# raspilot.net
KiCad netlist of a schematic drawn in EAGLE
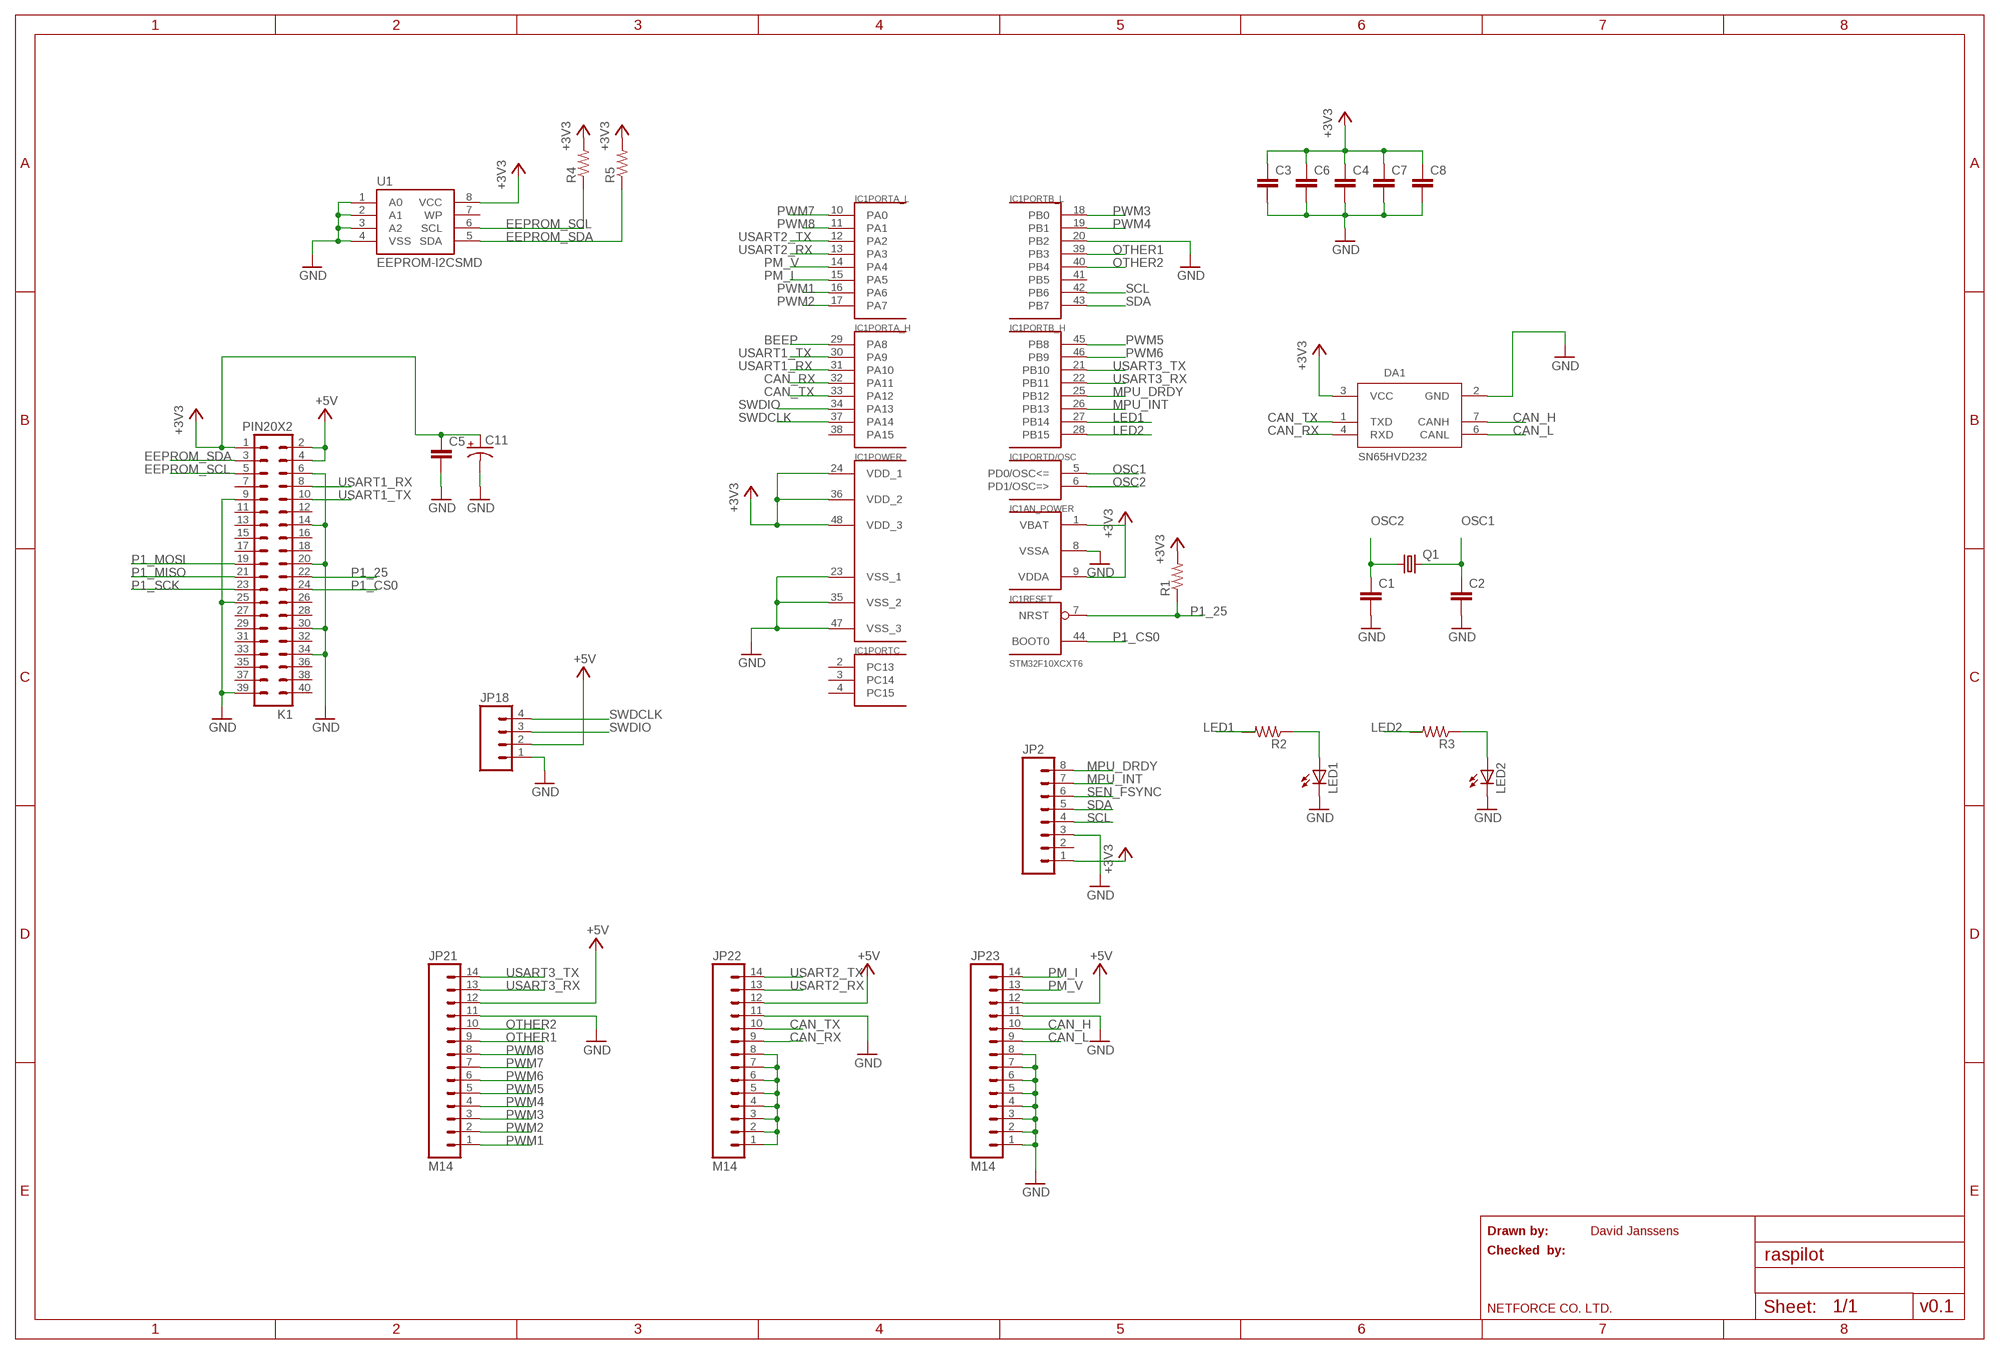
[diagram p0: schematic, sheet 1]

(export (version "E")
  (design (tool "Eeschema 10.0.6"))
  (components
    (comp (ref "C1")
      (value "CAP0805")
      (footprint "eagle-import:0805")
      (libsource (lib "eagle-import") (part "CAP0805"))
    )
    (comp (ref "C2")
      (value "CAP0805")
      (footprint "eagle-import:0805")
      (libsource (lib "eagle-import") (part "CAP0805"))
    )
    (comp (ref "C3")
      (value "CAP0805")
      (footprint "eagle-import:0805")
      (libsource (lib "eagle-import") (part "CAP0805"))
    )
    (comp (ref "C4")
      (value "CAP0805")
      (footprint "eagle-import:0805")
      (libsource (lib "eagle-import") (part "CAP0805"))
    )
    (comp (ref "C5")
      (value "CAP0805")
      (footprint "eagle-import:0805")
      (libsource (lib "eagle-import") (part "CAP0805"))
    )
    (comp (ref "C6")
      (value "CAP0805")
      (footprint "eagle-import:0805")
      (libsource (lib "eagle-import") (part "CAP0805"))
    )
    (comp (ref "C7")
      (value "CAP0805")
      (footprint "eagle-import:0805")
      (libsource (lib "eagle-import") (part "CAP0805"))
    )
    (comp (ref "C8")
      (value "CAP0805")
      (footprint "eagle-import:0805")
      (libsource (lib "eagle-import") (part "CAP0805"))
    )
    (comp (ref "C11")
      (value "CPOL-USE2.5-6")
      (footprint "eagle-import:E2,5-6")
      (libsource (lib "eagle-import") (part "CPOL-USE2.5-6"))
    )
    (comp (ref "DA1")
      (value "SN65HVD232")
      (footprint "eagle-import:SO08")
      (libsource (lib "eagle-import") (part "SN65HVD232"))
    )
    (comp (ref "IC1")
      (value "STM32F10XCXT6")
      (footprint "eagle-import:TQFP48")
      (libsource (lib "eagle-import") (part "STM32F10XCXT6"))
    )
    (comp (ref "JP2")
      (value "M08")
      (footprint "eagle-import:1X08_ROUND")
      (libsource (lib "eagle-import") (part "M08"))
    )
    (comp (ref "JP18")
      (value "M04PTH")
      (footprint "eagle-import:1X04")
      (libsource (lib "eagle-import") (part "M04PTH"))
    )
    (comp (ref "JP21")
      (value "M14")
      (footprint "eagle-import:1X14")
      (libsource (lib "eagle-import") (part "M14"))
    )
    (comp (ref "JP22")
      (value "M14")
      (footprint "eagle-import:1X14")
      (libsource (lib "eagle-import") (part "M14"))
    )
    (comp (ref "JP23")
      (value "M14")
      (footprint "eagle-import:1X14")
      (libsource (lib "eagle-import") (part "M14"))
    )
    (comp (ref "K1")
      (value "PIN20X2")
      (footprint "eagle-import:PIN_20X2")
      (libsource (lib "eagle-import") (part "PIN20X2"))
    )
    (comp (ref "LED1")
      (value "LED3MM")
      (footprint "eagle-import:LED3MM")
      (libsource (lib "eagle-import") (part "LED3MM"))
    )
    (comp (ref "LED2")
      (value "LED3MM")
      (footprint "eagle-import:LED3MM")
      (libsource (lib "eagle-import") (part "LED3MM"))
    )
    (comp (ref "Q1")
      (value "CRYSTALHC49S")
      (footprint "eagle-import:HC49_S")
      (libsource (lib "eagle-import") (part "CRYSTALHC49S"))
    )
    (comp (ref "R1")
      (value "RESISTOR0805-RES")
      (footprint "eagle-import:0805")
      (libsource (lib "eagle-import") (part "RESISTOR0805-RES"))
    )
    (comp (ref "R2")
      (value "RESISTOR0805-RES")
      (footprint "eagle-import:0805")
      (libsource (lib "eagle-import") (part "RESISTOR0805-RES"))
    )
    (comp (ref "R3")
      (value "RESISTOR0805-RES")
      (footprint "eagle-import:0805")
      (libsource (lib "eagle-import") (part "RESISTOR0805-RES"))
    )
    (comp (ref "R4")
      (value "RESISTOR0805-RES")
      (footprint "eagle-import:0805")
      (libsource (lib "eagle-import") (part "RESISTOR0805-RES"))
    )
    (comp (ref "R5")
      (value "RESISTOR0805-RES")
      (footprint "eagle-import:0805")
      (libsource (lib "eagle-import") (part "RESISTOR0805-RES"))
    )
    (comp (ref "U1")
      (value "EEPROM-I2CSMD")
      (footprint "eagle-import:SO08")
      (libsource (lib "eagle-import") (part "EEPROM-I2CSMD"))
    )
  )
  (nets
    (net (code "1") (name "+3V3") (class "Default")
      (node (ref "C11") (pin "+") (pinfunction "+_+") (pintype "passive"))
      (node (ref "C3") (pin "1") (pinfunction "1_1") (pintype "passive"))
      (node (ref "C4") (pin "1") (pinfunction "1_1") (pintype "passive"))
      (node (ref "C5") (pin "1") (pinfunction "1_1") (pintype "passive"))
      (node (ref "C6") (pin "1") (pinfunction "1_1") (pintype "passive"))
      (node (ref "C7") (pin "1") (pinfunction "1_1") (pintype "passive"))
      (node (ref "C8") (pin "1") (pinfunction "1_1") (pintype "passive"))
      (node (ref "DA1") (pin "3") (pinfunction "VCC_3") (pintype "power_in"))
      (node (ref "IC1") (pin "1") (pinfunction "VBAT_1") (pintype "power_in"))
      (node (ref "IC1") (pin "24") (pinfunction "VDD_1_24") (pintype "power_in"))
      (node (ref "IC1") (pin "36") (pinfunction "VDD_2_36") (pintype "power_in"))
      (node (ref "IC1") (pin "48") (pinfunction "VDD_3_48") (pintype "power_in"))
      (node (ref "IC1") (pin "9") (pinfunction "VDDA_9") (pintype "power_in"))
      (node (ref "JP2") (pin "1") (pinfunction "1_1") (pintype "passive"))
      (node (ref "K1") (pin "1") (pinfunction "1_1") (pintype "passive"))
      (node (ref "R1") (pin "2") (pinfunction "2_2") (pintype "passive"))
      (node (ref "R4") (pin "2") (pinfunction "2_2") (pintype "passive"))
      (node (ref "R5") (pin "2") (pinfunction "2_2") (pintype "passive"))
      (node (ref "U1") (pin "8") (pinfunction "VCC_8") (pintype "power_in"))
    )
    (net (code "2") (name "+5V") (class "Default")
      (node (ref "JP18") (pin "2") (pinfunction "2_2") (pintype "passive"))
      (node (ref "JP21") (pin "12") (pinfunction "12_12") (pintype "passive"))
      (node (ref "JP22") (pin "12") (pinfunction "12_12") (pintype "passive"))
      (node (ref "JP23") (pin "12") (pinfunction "12_12") (pintype "passive"))
      (node (ref "K1") (pin "2") (pinfunction "2_2") (pintype "passive"))
      (node (ref "K1") (pin "4") (pinfunction "4_4") (pintype "passive"))
    )
    (net (code "3") (name "/BEEP") (class "Default")
      (node (ref "IC1") (pin "29") (pinfunction "PA8_29") (pintype "bidirectional"))
    )
    (net (code "4") (name "/CAN_H") (class "Default")
      (node (ref "DA1") (pin "7") (pinfunction "CANH_7") (pintype "bidirectional"))
      (node (ref "JP23") (pin "10") (pinfunction "10_10") (pintype "passive"))
    )
    (net (code "5") (name "/CAN_L") (class "Default")
      (node (ref "DA1") (pin "6") (pinfunction "CANL_6") (pintype "bidirectional"))
      (node (ref "JP23") (pin "9") (pinfunction "9_9") (pintype "passive"))
    )
    (net (code "6") (name "/CAN_RX") (class "Default")
      (node (ref "DA1") (pin "4") (pinfunction "RXD_4") (pintype "output"))
      (node (ref "IC1") (pin "32") (pinfunction "PA11_32") (pintype "bidirectional"))
      (node (ref "JP22") (pin "9") (pinfunction "9_9") (pintype "passive"))
    )
    (net (code "7") (name "/CAN_TX") (class "Default")
      (node (ref "DA1") (pin "1") (pinfunction "TXD_1") (pintype "input"))
      (node (ref "IC1") (pin "33") (pinfunction "PA12_33") (pintype "bidirectional"))
      (node (ref "JP22") (pin "10") (pinfunction "10_10") (pintype "passive"))
    )
    (net (code "8") (name "/EEPROM_SCL") (class "Default")
      (node (ref "K1") (pin "5") (pinfunction "5_5") (pintype "passive"))
      (node (ref "R4") (pin "1") (pinfunction "1_1") (pintype "passive"))
      (node (ref "U1") (pin "6") (pinfunction "SCL_6") (pintype "bidirectional"))
    )
    (net (code "9") (name "/EEPROM_SDA") (class "Default")
      (node (ref "K1") (pin "3") (pinfunction "3_3") (pintype "passive"))
      (node (ref "R5") (pin "1") (pinfunction "1_1") (pintype "passive"))
      (node (ref "U1") (pin "5") (pinfunction "SDA_5") (pintype "bidirectional"))
    )
    (net (code "10") (name "/LED1") (class "Default")
      (node (ref "IC1") (pin "27") (pinfunction "PB14_27") (pintype "bidirectional"))
      (node (ref "R2") (pin "2") (pinfunction "2_2") (pintype "passive"))
    )
    (net (code "11") (name "/LED2") (class "Default")
      (node (ref "IC1") (pin "28") (pinfunction "PB15_28") (pintype "bidirectional"))
      (node (ref "R3") (pin "2") (pinfunction "2_2") (pintype "passive"))
    )
    (net (code "12") (name "/MPU_DRDY") (class "Default")
      (node (ref "IC1") (pin "25") (pinfunction "PB12_25") (pintype "bidirectional"))
      (node (ref "JP2") (pin "8") (pinfunction "8_8") (pintype "passive"))
    )
    (net (code "13") (name "/MPU_INT") (class "Default")
      (node (ref "IC1") (pin "26") (pinfunction "PB13_26") (pintype "bidirectional"))
      (node (ref "JP2") (pin "7") (pinfunction "7_7") (pintype "passive"))
    )
    (net (code "14") (name "/OSC1") (class "Default")
      (node (ref "C2") (pin "1") (pinfunction "1_1") (pintype "passive"))
      (node (ref "IC1") (pin "5") (pinfunction "PD0/OSC<=_5") (pintype "bidirectional"))
      (node (ref "Q1") (pin "2") (pinfunction "2_2") (pintype "passive"))
    )
    (net (code "15") (name "/OSC2") (class "Default")
      (node (ref "C1") (pin "1") (pinfunction "1_1") (pintype "passive"))
      (node (ref "IC1") (pin "6") (pinfunction "PD1/OSC=>_6") (pintype "bidirectional"))
      (node (ref "Q1") (pin "1") (pinfunction "1_1") (pintype "passive"))
    )
    (net (code "16") (name "/OTHER1") (class "Default")
      (node (ref "IC1") (pin "39") (pinfunction "PB3_39") (pintype "bidirectional"))
      (node (ref "JP21") (pin "9") (pinfunction "9_9") (pintype "passive"))
    )
    (net (code "17") (name "/OTHER2") (class "Default")
      (node (ref "IC1") (pin "40") (pinfunction "PB4_40") (pintype "bidirectional"))
      (node (ref "JP21") (pin "10") (pinfunction "10_10") (pintype "passive"))
    )
    (net (code "18") (name "/P1_25") (class "Default")
      (node (ref "IC1") (pin "7") (pinfunction "NRST_7") (pintype "input"))
      (node (ref "K1") (pin "22") (pinfunction "22_22") (pintype "passive"))
      (node (ref "R1") (pin "1") (pinfunction "1_1") (pintype "passive"))
    )
    (net (code "19") (name "/P1_CS0") (class "Default")
      (node (ref "IC1") (pin "44") (pinfunction "BOOT0_44") (pintype "input"))
      (node (ref "K1") (pin "24") (pinfunction "24_24") (pintype "passive"))
    )
    (net (code "20") (name "/P1_MISO") (class "Default")
      (node (ref "K1") (pin "21") (pinfunction "21_21") (pintype "passive"))
    )
    (net (code "21") (name "/P1_MOSI") (class "Default")
      (node (ref "K1") (pin "19") (pinfunction "19_19") (pintype "passive"))
    )
    (net (code "22") (name "/P1_SCK") (class "Default")
      (node (ref "K1") (pin "23") (pinfunction "23_23") (pintype "passive"))
    )
    (net (code "23") (name "/PM_I") (class "Default")
      (node (ref "IC1") (pin "15") (pinfunction "PA5_15") (pintype "bidirectional"))
      (node (ref "JP23") (pin "14") (pinfunction "14_14") (pintype "passive"))
    )
    (net (code "24") (name "/PM_V") (class "Default")
      (node (ref "IC1") (pin "14") (pinfunction "PA4_14") (pintype "bidirectional"))
      (node (ref "JP23") (pin "13") (pinfunction "13_13") (pintype "passive"))
    )
    (net (code "25") (name "/PWM1") (class "Default")
      (node (ref "IC1") (pin "16") (pinfunction "PA6_16") (pintype "bidirectional"))
      (node (ref "JP21") (pin "1") (pinfunction "1_1") (pintype "passive"))
    )
    (net (code "26") (name "/PWM2") (class "Default")
      (node (ref "IC1") (pin "17") (pinfunction "PA7_17") (pintype "bidirectional"))
      (node (ref "JP21") (pin "2") (pinfunction "2_2") (pintype "passive"))
    )
    (net (code "27") (name "/PWM3") (class "Default")
      (node (ref "IC1") (pin "18") (pinfunction "PB0_18") (pintype "bidirectional"))
      (node (ref "JP21") (pin "3") (pinfunction "3_3") (pintype "passive"))
    )
    (net (code "28") (name "/PWM4") (class "Default")
      (node (ref "IC1") (pin "19") (pinfunction "PB1_19") (pintype "bidirectional"))
      (node (ref "JP21") (pin "4") (pinfunction "4_4") (pintype "passive"))
    )
    (net (code "29") (name "/PWM5") (class "Default")
      (node (ref "IC1") (pin "45") (pinfunction "PB8_45") (pintype "bidirectional"))
      (node (ref "JP21") (pin "5") (pinfunction "5_5") (pintype "passive"))
    )
    (net (code "30") (name "/PWM6") (class "Default")
      (node (ref "IC1") (pin "46") (pinfunction "PB9_46") (pintype "bidirectional"))
      (node (ref "JP21") (pin "6") (pinfunction "6_6") (pintype "passive"))
    )
    (net (code "31") (name "/PWM7") (class "Default")
      (node (ref "IC1") (pin "10") (pinfunction "PA0_10") (pintype "bidirectional"))
      (node (ref "JP21") (pin "7") (pinfunction "7_7") (pintype "passive"))
    )
    (net (code "32") (name "/PWM8") (class "Default")
      (node (ref "IC1") (pin "11") (pinfunction "PA1_11") (pintype "bidirectional"))
      (node (ref "JP21") (pin "8") (pinfunction "8_8") (pintype "passive"))
    )
    (net (code "33") (name "/SCL") (class "Default")
      (node (ref "IC1") (pin "42") (pinfunction "PB6_42") (pintype "bidirectional"))
      (node (ref "JP2") (pin "4") (pinfunction "4_4") (pintype "passive"))
    )
    (net (code "34") (name "/SDA") (class "Default")
      (node (ref "IC1") (pin "43") (pinfunction "PB7_43") (pintype "bidirectional"))
      (node (ref "JP2") (pin "5") (pinfunction "5_5") (pintype "passive"))
    )
    (net (code "35") (name "/SEN_FSYNC") (class "Default")
      (node (ref "JP2") (pin "6") (pinfunction "6_6") (pintype "passive"))
    )
    (net (code "36") (name "/SWDCLK") (class "Default")
      (node (ref "IC1") (pin "37") (pinfunction "PA14_37") (pintype "bidirectional"))
      (node (ref "JP18") (pin "4") (pinfunction "4_4") (pintype "passive"))
    )
    (net (code "37") (name "/SWDIO") (class "Default")
      (node (ref "IC1") (pin "34") (pinfunction "PA13_34") (pintype "bidirectional"))
      (node (ref "JP18") (pin "3") (pinfunction "3_3") (pintype "passive"))
    )
    (net (code "38") (name "/USART1_RX") (class "Default")
      (node (ref "IC1") (pin "31") (pinfunction "PA10_31") (pintype "bidirectional"))
      (node (ref "K1") (pin "8") (pinfunction "8_8") (pintype "passive"))
    )
    (net (code "39") (name "/USART1_TX") (class "Default")
      (node (ref "IC1") (pin "30") (pinfunction "PA9_30") (pintype "bidirectional"))
      (node (ref "K1") (pin "10") (pinfunction "10_10") (pintype "passive"))
    )
    (net (code "40") (name "/USART2_RX") (class "Default")
      (node (ref "IC1") (pin "13") (pinfunction "PA3_13") (pintype "bidirectional"))
      (node (ref "JP22") (pin "13") (pinfunction "13_13") (pintype "passive"))
    )
    (net (code "41") (name "/USART2_TX") (class "Default")
      (node (ref "IC1") (pin "12") (pinfunction "PA2_12") (pintype "bidirectional"))
      (node (ref "JP22") (pin "14") (pinfunction "14_14") (pintype "passive"))
    )
    (net (code "42") (name "/USART3_RX") (class "Default")
      (node (ref "IC1") (pin "22") (pinfunction "PB11_22") (pintype "bidirectional"))
      (node (ref "JP21") (pin "13") (pinfunction "13_13") (pintype "passive"))
    )
    (net (code "43") (name "/USART3_TX") (class "Default")
      (node (ref "IC1") (pin "21") (pinfunction "PB10_21") (pintype "bidirectional"))
      (node (ref "JP21") (pin "14") (pinfunction "14_14") (pintype "passive"))
    )
    (net (code "44") (name "GND") (class "Default")
      (node (ref "C1") (pin "2") (pinfunction "2_2") (pintype "passive"))
      (node (ref "C11") (pin "-") (pinfunction "-_-") (pintype "passive"))
      (node (ref "C2") (pin "2") (pinfunction "2_2") (pintype "passive"))
      (node (ref "C3") (pin "2") (pinfunction "2_2") (pintype "passive"))
      (node (ref "C4") (pin "2") (pinfunction "2_2") (pintype "passive"))
      (node (ref "C5") (pin "2") (pinfunction "2_2") (pintype "passive"))
      (node (ref "C6") (pin "2") (pinfunction "2_2") (pintype "passive"))
      (node (ref "C7") (pin "2") (pinfunction "2_2") (pintype "passive"))
      (node (ref "C8") (pin "2") (pinfunction "2_2") (pintype "passive"))
      (node (ref "DA1") (pin "2") (pinfunction "GND_2") (pintype "power_in"))
      (node (ref "IC1") (pin "20") (pinfunction "PB2_20") (pintype "bidirectional"))
      (node (ref "IC1") (pin "23") (pinfunction "VSS_1_23") (pintype "power_in"))
      (node (ref "IC1") (pin "35") (pinfunction "VSS_2_35") (pintype "power_in"))
      (node (ref "IC1") (pin "47") (pinfunction "VSS_3_47") (pintype "power_in"))
      (node (ref "IC1") (pin "8") (pinfunction "VSSA_8") (pintype "power_in"))
      (node (ref "JP18") (pin "1") (pinfunction "1_1") (pintype "passive"))
      (node (ref "JP2") (pin "3") (pinfunction "3_3") (pintype "passive"))
      (node (ref "JP21") (pin "11") (pinfunction "11_11") (pintype "passive"))
      (node (ref "JP22") (pin "11") (pinfunction "11_11") (pintype "passive"))
      (node (ref "JP23") (pin "1") (pinfunction "1_1") (pintype "passive"))
      (node (ref "JP23") (pin "11") (pinfunction "11_11") (pintype "passive"))
      (node (ref "JP23") (pin "2") (pinfunction "2_2") (pintype "passive"))
      (node (ref "JP23") (pin "3") (pinfunction "3_3") (pintype "passive"))
      (node (ref "JP23") (pin "4") (pinfunction "4_4") (pintype "passive"))
      (node (ref "JP23") (pin "5") (pinfunction "5_5") (pintype "passive"))
      (node (ref "JP23") (pin "6") (pinfunction "6_6") (pintype "passive"))
      (node (ref "JP23") (pin "7") (pinfunction "7_7") (pintype "passive"))
      (node (ref "JP23") (pin "8") (pinfunction "8_8") (pintype "passive"))
      (node (ref "K1") (pin "14") (pinfunction "14_14") (pintype "passive"))
      (node (ref "K1") (pin "20") (pinfunction "20_20") (pintype "passive"))
      (node (ref "K1") (pin "25") (pinfunction "25_25") (pintype "passive"))
      (node (ref "K1") (pin "30") (pinfunction "30_30") (pintype "passive"))
      (node (ref "K1") (pin "34") (pinfunction "34_34") (pintype "passive"))
      (node (ref "K1") (pin "39") (pinfunction "39_39") (pintype "passive"))
      (node (ref "K1") (pin "6") (pinfunction "6_6") (pintype "passive"))
      (node (ref "K1") (pin "9") (pinfunction "9_9") (pintype "passive"))
      (node (ref "LED1") (pin "K") (pinfunction "C_K") (pintype "passive"))
      (node (ref "LED2") (pin "K") (pinfunction "C_K") (pintype "passive"))
      (node (ref "U1") (pin "1") (pinfunction "A0_1") (pintype "bidirectional"))
      (node (ref "U1") (pin "2") (pinfunction "A1_2") (pintype "bidirectional"))
      (node (ref "U1") (pin "3") (pinfunction "A2_3") (pintype "bidirectional"))
      (node (ref "U1") (pin "4") (pinfunction "VSS_4") (pintype "power_in"))
    )
    (net (code "45") (name "Net-(JP22-Pad1)") (class "Default")
      (node (ref "JP22") (pin "1") (pinfunction "1_1") (pintype "passive"))
      (node (ref "JP22") (pin "2") (pinfunction "2_2") (pintype "passive"))
      (node (ref "JP22") (pin "3") (pinfunction "3_3") (pintype "passive"))
      (node (ref "JP22") (pin "4") (pinfunction "4_4") (pintype "passive"))
      (node (ref "JP22") (pin "5") (pinfunction "5_5") (pintype "passive"))
      (node (ref "JP22") (pin "6") (pinfunction "6_6") (pintype "passive"))
      (node (ref "JP22") (pin "7") (pinfunction "7_7") (pintype "passive"))
      (node (ref "JP22") (pin "8") (pinfunction "8_8") (pintype "passive"))
    )
    (net (code "46") (name "Net-(LED1-PadA)") (class "Default")
      (node (ref "LED1") (pin "A") (pinfunction "A_A") (pintype "passive"))
      (node (ref "R2") (pin "1") (pinfunction "1_1") (pintype "passive"))
    )
    (net (code "47") (name "Net-(LED2-PadA)") (class "Default")
      (node (ref "LED2") (pin "A") (pinfunction "A_A") (pintype "passive"))
      (node (ref "R3") (pin "1") (pinfunction "1_1") (pintype "passive"))
    )
    (net (code "48") (name "unconnected-(IC1B-PA15-Pad38)") (class "Default")
      (node (ref "IC1") (pin "38") (pinfunction "PA15_38") (pintype "bidirectional"))
    )
    (net (code "49") (name "unconnected-(IC1E-PB5-Pad41)") (class "Default")
      (node (ref "IC1") (pin "41") (pinfunction "PB5_41") (pintype "bidirectional"))
    )
    (net (code "50") (name "unconnected-(IC1F-PC13-Pad2)") (class "Default")
      (node (ref "IC1") (pin "2") (pinfunction "PC13_2") (pintype "bidirectional"))
    )
    (net (code "51") (name "unconnected-(IC1F-PC14-Pad3)") (class "Default")
      (node (ref "IC1") (pin "3") (pinfunction "PC14_3") (pintype "bidirectional"))
    )
    (net (code "52") (name "unconnected-(IC1F-PC15-Pad4)") (class "Default")
      (node (ref "IC1") (pin "4") (pinfunction "PC15_4") (pintype "bidirectional"))
    )
    (net (code "53") (name "unconnected-(JP2-Pad2)") (class "Default")
      (node (ref "JP2") (pin "2") (pinfunction "2_2") (pintype "passive"))
    )
    (net (code "54") (name "unconnected-(K1-Pad7)") (class "Default")
      (node (ref "K1") (pin "7") (pinfunction "7_7") (pintype "passive"))
    )
    (net (code "55") (name "unconnected-(K1-Pad11)") (class "Default")
      (node (ref "K1") (pin "11") (pinfunction "11_11") (pintype "passive"))
    )
    (net (code "56") (name "unconnected-(K1-Pad12)") (class "Default")
      (node (ref "K1") (pin "12") (pinfunction "12_12") (pintype "passive"))
    )
    (net (code "57") (name "unconnected-(K1-Pad13)") (class "Default")
      (node (ref "K1") (pin "13") (pinfunction "13_13") (pintype "passive"))
    )
    (net (code "58") (name "unconnected-(K1-Pad15)") (class "Default")
      (node (ref "K1") (pin "15") (pinfunction "15_15") (pintype "passive"))
    )
    (net (code "59") (name "unconnected-(K1-Pad16)") (class "Default")
      (node (ref "K1") (pin "16") (pinfunction "16_16") (pintype "passive"))
    )
    (net (code "60") (name "unconnected-(K1-Pad17)") (class "Default")
      (node (ref "K1") (pin "17") (pinfunction "17_17") (pintype "passive"))
    )
    (net (code "61") (name "unconnected-(K1-Pad18)") (class "Default")
      (node (ref "K1") (pin "18") (pinfunction "18_18") (pintype "passive"))
    )
    (net (code "62") (name "unconnected-(K1-Pad26)") (class "Default")
      (node (ref "K1") (pin "26") (pinfunction "26_26") (pintype "passive"))
    )
    (net (code "63") (name "unconnected-(K1-Pad27)") (class "Default")
      (node (ref "K1") (pin "27") (pinfunction "27_27") (pintype "passive"))
    )
    (net (code "64") (name "unconnected-(K1-Pad28)") (class "Default")
      (node (ref "K1") (pin "28") (pinfunction "28_28") (pintype "passive"))
    )
    (net (code "65") (name "unconnected-(K1-Pad29)") (class "Default")
      (node (ref "K1") (pin "29") (pinfunction "29_29") (pintype "passive"))
    )
    (net (code "66") (name "unconnected-(K1-Pad31)") (class "Default")
      (node (ref "K1") (pin "31") (pinfunction "31_31") (pintype "passive"))
    )
    (net (code "67") (name "unconnected-(K1-Pad32)") (class "Default")
      (node (ref "K1") (pin "32") (pinfunction "32_32") (pintype "passive"))
    )
    (net (code "68") (name "unconnected-(K1-Pad33)") (class "Default")
      (node (ref "K1") (pin "33") (pinfunction "33_33") (pintype "passive"))
    )
    (net (code "69") (name "unconnected-(K1-Pad35)") (class "Default")
      (node (ref "K1") (pin "35") (pinfunction "35_35") (pintype "passive"))
    )
    (net (code "70") (name "unconnected-(K1-Pad36)") (class "Default")
      (node (ref "K1") (pin "36") (pinfunction "36_36") (pintype "passive"))
    )
    (net (code "71") (name "unconnected-(K1-Pad37)") (class "Default")
      (node (ref "K1") (pin "37") (pinfunction "37_37") (pintype "passive"))
    )
    (net (code "72") (name "unconnected-(K1-Pad38)") (class "Default")
      (node (ref "K1") (pin "38") (pinfunction "38_38") (pintype "passive"))
    )
    (net (code "73") (name "unconnected-(K1-Pad40)") (class "Default")
      (node (ref "K1") (pin "40") (pinfunction "40_40") (pintype "passive"))
    )
    (net (code "74") (name "unconnected-(U1-WP-Pad7)") (class "Default")
      (node (ref "U1") (pin "7") (pinfunction "WP_7") (pintype "bidirectional"))
    )
  )
)
